# IPSv1_0.net
KiCad netlist of a schematic drawn in EAGLE
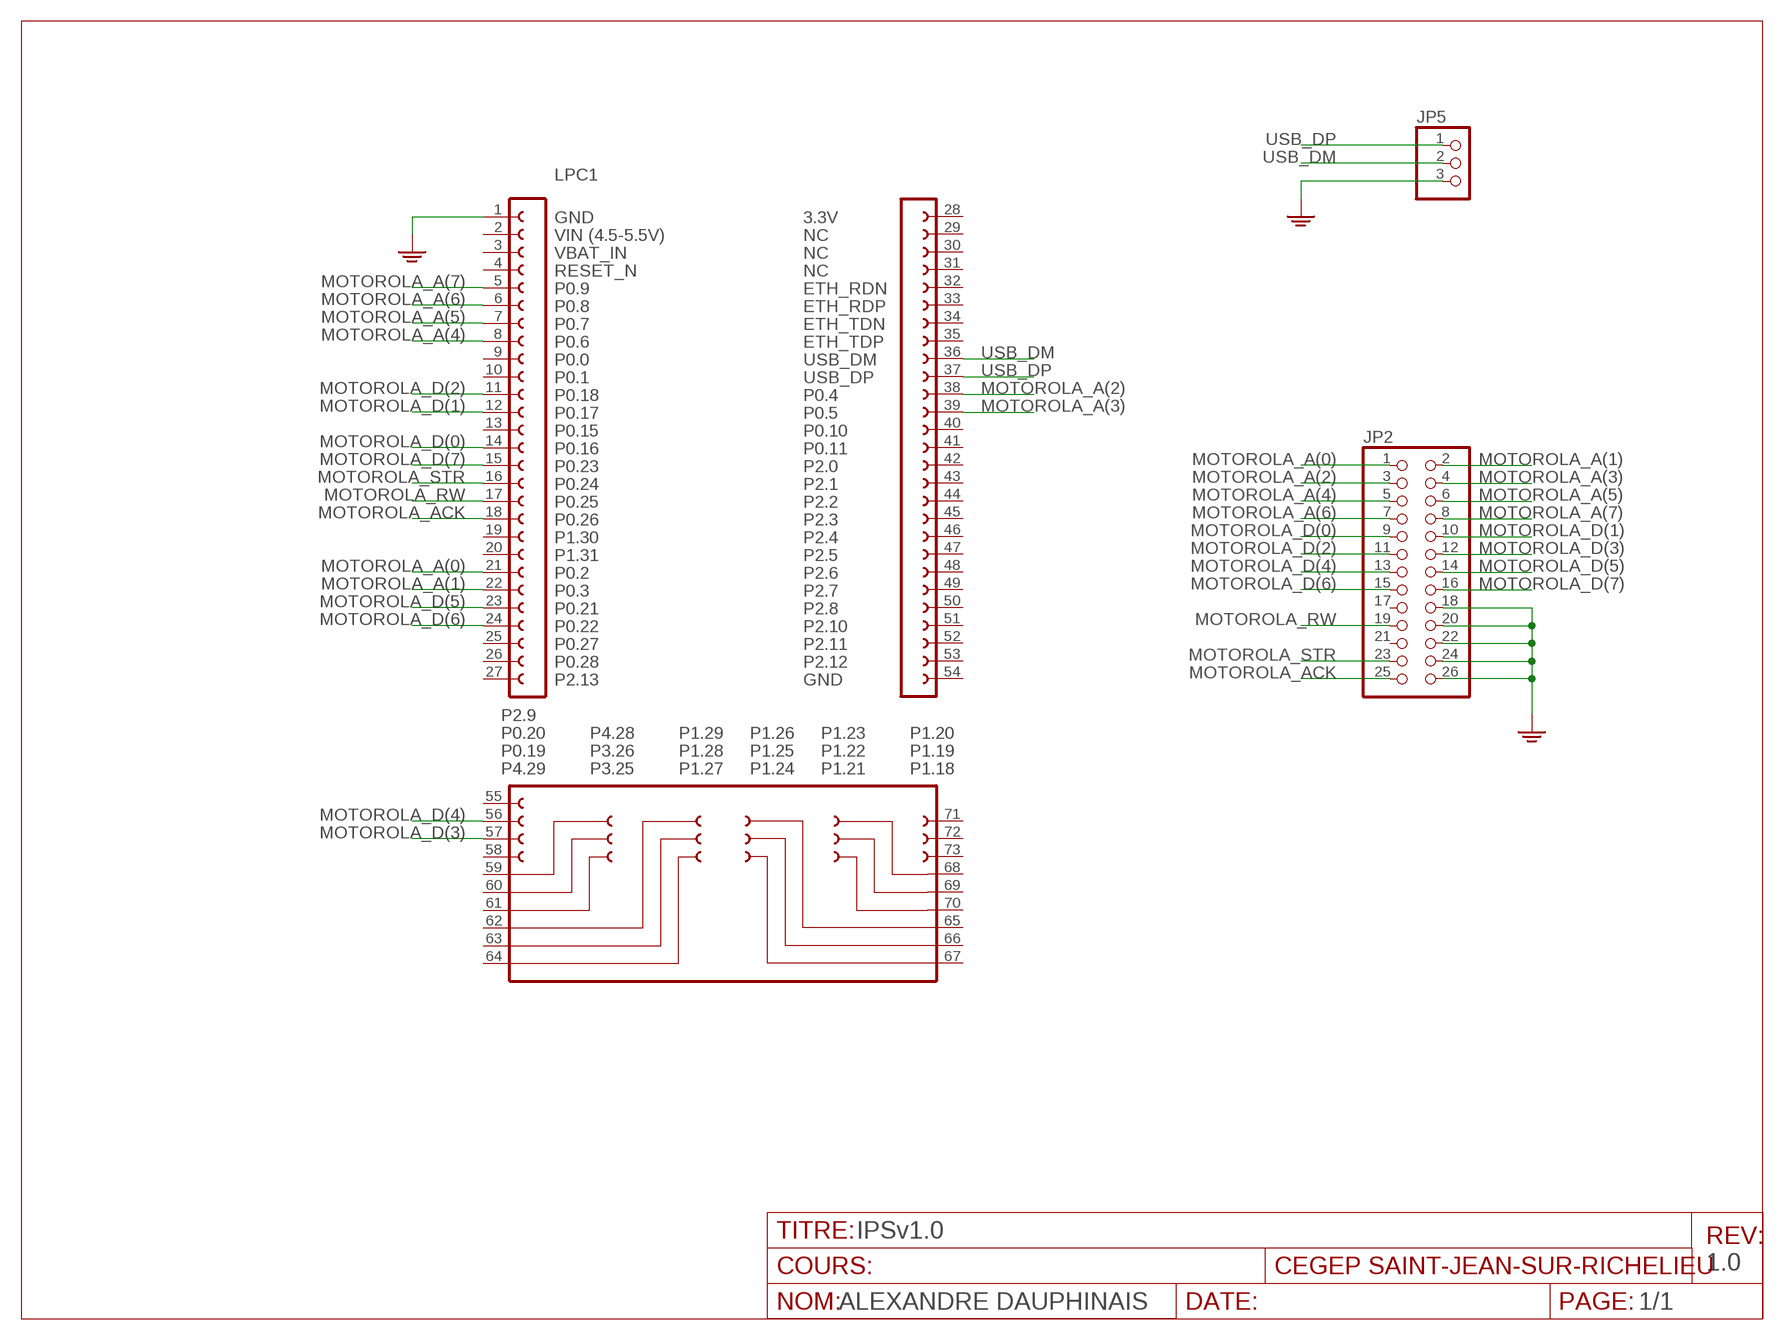
[diagram p0: schematic, sheet 1]

(export (version "E")
  (design (tool "Eeschema 10.0.6"))
  (components
    (comp (ref "JP2")
      (value "PINHD-2X13")
      (footprint "eagle-import:2X13")
      (libsource (lib "eagle-import") (part "PINHD-2X13"))
    )
    (comp (ref "JP5")
      (value "PINHD-1X3")
      (footprint "eagle-import:1X03")
      (libsource (lib "eagle-import") (part "PINHD-1X3"))
    )
    (comp (ref "LPC1")
      (value "LPCXPRESSO_LPC1769")
      (footprint "eagle-import:LPCXPRESSO_LPC1769")
      (libsource (lib "eagle-import") (part "LPCXPRESSO_LPC1769"))
    )
  )
  (nets
    (net (code "1") (name "/MOTOROLA_A(0)") (class "Default")
      (node (ref "JP2") (pin "1") (pinfunction "1_1") (pintype "passive"))
      (node (ref "LPC1") (pin "21") (pinfunction "21_21") (pintype "passive"))
    )
    (net (code "2") (name "/MOTOROLA_A(1)") (class "Default")
      (node (ref "JP2") (pin "2") (pinfunction "2_2") (pintype "passive"))
      (node (ref "LPC1") (pin "22") (pinfunction "22_22") (pintype "passive"))
    )
    (net (code "3") (name "/MOTOROLA_A(2)") (class "Default")
      (node (ref "JP2") (pin "3") (pinfunction "3_3") (pintype "passive"))
      (node (ref "LPC1") (pin "38") (pinfunction "38_38") (pintype "passive"))
    )
    (net (code "4") (name "/MOTOROLA_A(3)") (class "Default")
      (node (ref "JP2") (pin "4") (pinfunction "4_4") (pintype "passive"))
      (node (ref "LPC1") (pin "39") (pinfunction "39_39") (pintype "passive"))
    )
    (net (code "5") (name "/MOTOROLA_A(4)") (class "Default")
      (node (ref "JP2") (pin "5") (pinfunction "5_5") (pintype "passive"))
      (node (ref "LPC1") (pin "8") (pinfunction "8_8") (pintype "passive"))
    )
    (net (code "6") (name "/MOTOROLA_A(5)") (class "Default")
      (node (ref "JP2") (pin "6") (pinfunction "6_6") (pintype "passive"))
      (node (ref "LPC1") (pin "7") (pinfunction "7_7") (pintype "passive"))
    )
    (net (code "7") (name "/MOTOROLA_A(6)") (class "Default")
      (node (ref "JP2") (pin "7") (pinfunction "7_7") (pintype "passive"))
      (node (ref "LPC1") (pin "6") (pinfunction "6_6") (pintype "passive"))
    )
    (net (code "8") (name "/MOTOROLA_A(7)") (class "Default")
      (node (ref "JP2") (pin "8") (pinfunction "8_8") (pintype "passive"))
      (node (ref "LPC1") (pin "5") (pinfunction "5_5") (pintype "passive"))
    )
    (net (code "9") (name "/MOTOROLA_ACK") (class "Default")
      (node (ref "JP2") (pin "25") (pinfunction "25_25") (pintype "passive"))
      (node (ref "LPC1") (pin "18") (pinfunction "18_18") (pintype "passive"))
    )
    (net (code "10") (name "/MOTOROLA_D(0)") (class "Default")
      (node (ref "JP2") (pin "9") (pinfunction "9_9") (pintype "passive"))
      (node (ref "LPC1") (pin "14") (pinfunction "14_14") (pintype "passive"))
    )
    (net (code "11") (name "/MOTOROLA_D(1)") (class "Default")
      (node (ref "JP2") (pin "10") (pinfunction "10_10") (pintype "passive"))
      (node (ref "LPC1") (pin "12") (pinfunction "12_12") (pintype "passive"))
    )
    (net (code "12") (name "/MOTOROLA_D(2)") (class "Default")
      (node (ref "JP2") (pin "11") (pinfunction "11_11") (pintype "passive"))
      (node (ref "LPC1") (pin "11") (pinfunction "11_11") (pintype "passive"))
    )
    (net (code "13") (name "/MOTOROLA_D(3)") (class "Default")
      (node (ref "JP2") (pin "12") (pinfunction "12_12") (pintype "passive"))
      (node (ref "LPC1") (pin "57") (pinfunction "57_57") (pintype "passive"))
    )
    (net (code "14") (name "/MOTOROLA_D(4)") (class "Default")
      (node (ref "JP2") (pin "13") (pinfunction "13_13") (pintype "passive"))
      (node (ref "LPC1") (pin "56") (pinfunction "56_56") (pintype "passive"))
    )
    (net (code "15") (name "/MOTOROLA_D(5)") (class "Default")
      (node (ref "JP2") (pin "14") (pinfunction "14_14") (pintype "passive"))
      (node (ref "LPC1") (pin "23") (pinfunction "23_23") (pintype "passive"))
    )
    (net (code "16") (name "/MOTOROLA_D(6)") (class "Default")
      (node (ref "JP2") (pin "15") (pinfunction "15_15") (pintype "passive"))
      (node (ref "LPC1") (pin "24") (pinfunction "24_24") (pintype "passive"))
    )
    (net (code "17") (name "/MOTOROLA_D(7)") (class "Default")
      (node (ref "JP2") (pin "16") (pinfunction "16_16") (pintype "passive"))
      (node (ref "LPC1") (pin "15") (pinfunction "15_15") (pintype "passive"))
    )
    (net (code "18") (name "/MOTOROLA_RW") (class "Default")
      (node (ref "JP2") (pin "19") (pinfunction "19_19") (pintype "passive"))
      (node (ref "LPC1") (pin "17") (pinfunction "17_17") (pintype "passive"))
    )
    (net (code "19") (name "/MOTOROLA_STR") (class "Default")
      (node (ref "JP2") (pin "23") (pinfunction "23_23") (pintype "passive"))
      (node (ref "LPC1") (pin "16") (pinfunction "16_16") (pintype "passive"))
    )
    (net (code "20") (name "/USB_DM") (class "Default")
      (node (ref "JP5") (pin "2") (pinfunction "2_2") (pintype "passive"))
      (node (ref "LPC1") (pin "36") (pinfunction "36_36") (pintype "passive"))
    )
    (net (code "21") (name "/USB_DP") (class "Default")
      (node (ref "JP5") (pin "1") (pinfunction "1_1") (pintype "passive"))
      (node (ref "LPC1") (pin "37") (pinfunction "37_37") (pintype "passive"))
    )
    (net (code "22") (name "GND") (class "Default")
      (node (ref "JP2") (pin "18") (pinfunction "18_18") (pintype "passive"))
      (node (ref "JP2") (pin "20") (pinfunction "20_20") (pintype "passive"))
      (node (ref "JP2") (pin "22") (pinfunction "22_22") (pintype "passive"))
      (node (ref "JP2") (pin "24") (pinfunction "24_24") (pintype "passive"))
      (node (ref "JP2") (pin "26") (pinfunction "26_26") (pintype "passive"))
      (node (ref "JP5") (pin "3") (pinfunction "3_3") (pintype "passive"))
      (node (ref "LPC1") (pin "1") (pinfunction "1_1") (pintype "passive"))
    )
    (net (code "23") (name "unconnected-(JP2-Pad17)") (class "Default")
      (node (ref "JP2") (pin "17") (pinfunction "17_17") (pintype "passive"))
    )
    (net (code "24") (name "unconnected-(JP2-Pad21)") (class "Default")
      (node (ref "JP2") (pin "21") (pinfunction "21_21") (pintype "passive"))
    )
    (net (code "25") (name "unconnected-(LPC1-Pad2)") (class "Default")
      (node (ref "LPC1") (pin "2") (pinfunction "2_2") (pintype "passive"))
    )
    (net (code "26") (name "unconnected-(LPC1-Pad3)") (class "Default")
      (node (ref "LPC1") (pin "3") (pinfunction "3_3") (pintype "passive"))
    )
    (net (code "27") (name "unconnected-(LPC1-Pad4)") (class "Default")
      (node (ref "LPC1") (pin "4") (pinfunction "4_4") (pintype "passive"))
    )
    (net (code "28") (name "unconnected-(LPC1-Pad9)") (class "Default")
      (node (ref "LPC1") (pin "9") (pinfunction "9_9") (pintype "passive"))
    )
    (net (code "29") (name "unconnected-(LPC1-Pad10)") (class "Default")
      (node (ref "LPC1") (pin "10") (pinfunction "10_10") (pintype "passive"))
    )
    (net (code "30") (name "unconnected-(LPC1-Pad13)") (class "Default")
      (node (ref "LPC1") (pin "13") (pinfunction "13_13") (pintype "passive"))
    )
    (net (code "31") (name "unconnected-(LPC1-Pad19)") (class "Default")
      (node (ref "LPC1") (pin "19") (pinfunction "19_19") (pintype "passive"))
    )
    (net (code "32") (name "unconnected-(LPC1-Pad20)") (class "Default")
      (node (ref "LPC1") (pin "20") (pinfunction "20_20") (pintype "passive"))
    )
    (net (code "33") (name "unconnected-(LPC1-Pad25)") (class "Default")
      (node (ref "LPC1") (pin "25") (pinfunction "25_25") (pintype "passive"))
    )
    (net (code "34") (name "unconnected-(LPC1-Pad26)") (class "Default")
      (node (ref "LPC1") (pin "26") (pinfunction "26_26") (pintype "passive"))
    )
    (net (code "35") (name "unconnected-(LPC1-Pad27)") (class "Default")
      (node (ref "LPC1") (pin "27") (pinfunction "27_27") (pintype "passive"))
    )
    (net (code "36") (name "unconnected-(LPC1-Pad28)") (class "Default")
      (node (ref "LPC1") (pin "28") (pinfunction "28_28") (pintype "passive"))
    )
    (net (code "37") (name "unconnected-(LPC1-Pad29)") (class "Default")
      (node (ref "LPC1") (pin "29") (pinfunction "29_29") (pintype "passive"))
    )
    (net (code "38") (name "unconnected-(LPC1-Pad30)") (class "Default")
      (node (ref "LPC1") (pin "30") (pinfunction "30_30") (pintype "passive"))
    )
    (net (code "39") (name "unconnected-(LPC1-Pad31)") (class "Default")
      (node (ref "LPC1") (pin "31") (pinfunction "31_31") (pintype "passive"))
    )
    (net (code "40") (name "unconnected-(LPC1-Pad32)") (class "Default")
      (node (ref "LPC1") (pin "32") (pinfunction "32_32") (pintype "passive"))
    )
    (net (code "41") (name "unconnected-(LPC1-Pad33)") (class "Default")
      (node (ref "LPC1") (pin "33") (pinfunction "33_33") (pintype "passive"))
    )
    (net (code "42") (name "unconnected-(LPC1-Pad34)") (class "Default")
      (node (ref "LPC1") (pin "34") (pinfunction "34_34") (pintype "passive"))
    )
    (net (code "43") (name "unconnected-(LPC1-Pad35)") (class "Default")
      (node (ref "LPC1") (pin "35") (pinfunction "35_35") (pintype "passive"))
    )
    (net (code "44") (name "unconnected-(LPC1-Pad40)") (class "Default")
      (node (ref "LPC1") (pin "40") (pinfunction "40_40") (pintype "passive"))
    )
    (net (code "45") (name "unconnected-(LPC1-Pad41)") (class "Default")
      (node (ref "LPC1") (pin "41") (pinfunction "41_41") (pintype "passive"))
    )
    (net (code "46") (name "unconnected-(LPC1-Pad42)") (class "Default")
      (node (ref "LPC1") (pin "42") (pinfunction "42_42") (pintype "passive"))
    )
    (net (code "47") (name "unconnected-(LPC1-Pad43)") (class "Default")
      (node (ref "LPC1") (pin "43") (pinfunction "43_43") (pintype "passive"))
    )
    (net (code "48") (name "unconnected-(LPC1-Pad44)") (class "Default")
      (node (ref "LPC1") (pin "44") (pinfunction "44_44") (pintype "passive"))
    )
    (net (code "49") (name "unconnected-(LPC1-Pad45)") (class "Default")
      (node (ref "LPC1") (pin "45") (pinfunction "45_45") (pintype "passive"))
    )
    (net (code "50") (name "unconnected-(LPC1-Pad46)") (class "Default")
      (node (ref "LPC1") (pin "46") (pinfunction "46_46") (pintype "passive"))
    )
    (net (code "51") (name "unconnected-(LPC1-Pad47)") (class "Default")
      (node (ref "LPC1") (pin "47") (pinfunction "47_47") (pintype "passive"))
    )
    (net (code "52") (name "unconnected-(LPC1-Pad48)") (class "Default")
      (node (ref "LPC1") (pin "48") (pinfunction "48_48") (pintype "passive"))
    )
    (net (code "53") (name "unconnected-(LPC1-Pad49)") (class "Default")
      (node (ref "LPC1") (pin "49") (pinfunction "49_49") (pintype "passive"))
    )
    (net (code "54") (name "unconnected-(LPC1-Pad50)") (class "Default")
      (node (ref "LPC1") (pin "50") (pinfunction "50_50") (pintype "passive"))
    )
    (net (code "55") (name "unconnected-(LPC1-Pad51)") (class "Default")
      (node (ref "LPC1") (pin "51") (pinfunction "51_51") (pintype "passive"))
    )
    (net (code "56") (name "unconnected-(LPC1-Pad52)") (class "Default")
      (node (ref "LPC1") (pin "52") (pinfunction "52_52") (pintype "passive"))
    )
    (net (code "57") (name "unconnected-(LPC1-Pad53)") (class "Default")
      (node (ref "LPC1") (pin "53") (pinfunction "53_53") (pintype "passive"))
    )
    (net (code "58") (name "unconnected-(LPC1-Pad54)") (class "Default")
      (node (ref "LPC1") (pin "54") (pinfunction "54_54") (pintype "passive"))
    )
    (net (code "59") (name "unconnected-(LPC1-Pad55)") (class "Default")
      (node (ref "LPC1") (pin "55") (pinfunction "55_55") (pintype "passive"))
    )
    (net (code "60") (name "unconnected-(LPC1-Pad58)") (class "Default")
      (node (ref "LPC1") (pin "58") (pinfunction "58_58") (pintype "passive"))
    )
    (net (code "61") (name "unconnected-(LPC1-Pad59)") (class "Default")
      (node (ref "LPC1") (pin "59") (pinfunction "59_59") (pintype "passive"))
    )
    (net (code "62") (name "unconnected-(LPC1-Pad60)") (class "Default")
      (node (ref "LPC1") (pin "60") (pinfunction "60_60") (pintype "passive"))
    )
    (net (code "63") (name "unconnected-(LPC1-Pad61)") (class "Default")
      (node (ref "LPC1") (pin "61") (pinfunction "61_61") (pintype "passive"))
    )
    (net (code "64") (name "unconnected-(LPC1-Pad62)") (class "Default")
      (node (ref "LPC1") (pin "62") (pinfunction "62_62") (pintype "passive"))
    )
    (net (code "65") (name "unconnected-(LPC1-Pad63)") (class "Default")
      (node (ref "LPC1") (pin "63") (pinfunction "63_63") (pintype "passive"))
    )
    (net (code "66") (name "unconnected-(LPC1-Pad64)") (class "Default")
      (node (ref "LPC1") (pin "64") (pinfunction "64_64") (pintype "passive"))
    )
    (net (code "67") (name "unconnected-(LPC1-Pad65)") (class "Default")
      (node (ref "LPC1") (pin "65") (pinfunction "65_65") (pintype "passive"))
    )
    (net (code "68") (name "unconnected-(LPC1-Pad66)") (class "Default")
      (node (ref "LPC1") (pin "66") (pinfunction "66_66") (pintype "passive"))
    )
    (net (code "69") (name "unconnected-(LPC1-Pad67)") (class "Default")
      (node (ref "LPC1") (pin "67") (pinfunction "67_67") (pintype "passive"))
    )
    (net (code "70") (name "unconnected-(LPC1-Pad68)") (class "Default")
      (node (ref "LPC1") (pin "68") (pinfunction "68_68") (pintype "passive"))
    )
    (net (code "71") (name "unconnected-(LPC1-Pad69)") (class "Default")
      (node (ref "LPC1") (pin "69") (pinfunction "69_69") (pintype "passive"))
    )
    (net (code "72") (name "unconnected-(LPC1-Pad70)") (class "Default")
      (node (ref "LPC1") (pin "70") (pinfunction "70_70") (pintype "passive"))
    )
    (net (code "73") (name "unconnected-(LPC1-Pad71)") (class "Default")
      (node (ref "LPC1") (pin "71") (pinfunction "71_71") (pintype "passive"))
    )
    (net (code "74") (name "unconnected-(LPC1-Pad72)") (class "Default")
      (node (ref "LPC1") (pin "72") (pinfunction "72_72") (pintype "passive"))
    )
    (net (code "75") (name "unconnected-(LPC1-Pad73)") (class "Default")
      (node (ref "LPC1") (pin "73") (pinfunction "73_73") (pintype "passive"))
    )
  )
)
